# AUDIO_CODEC.net
KiCad netlist of a schematic drawn in Altium Designer
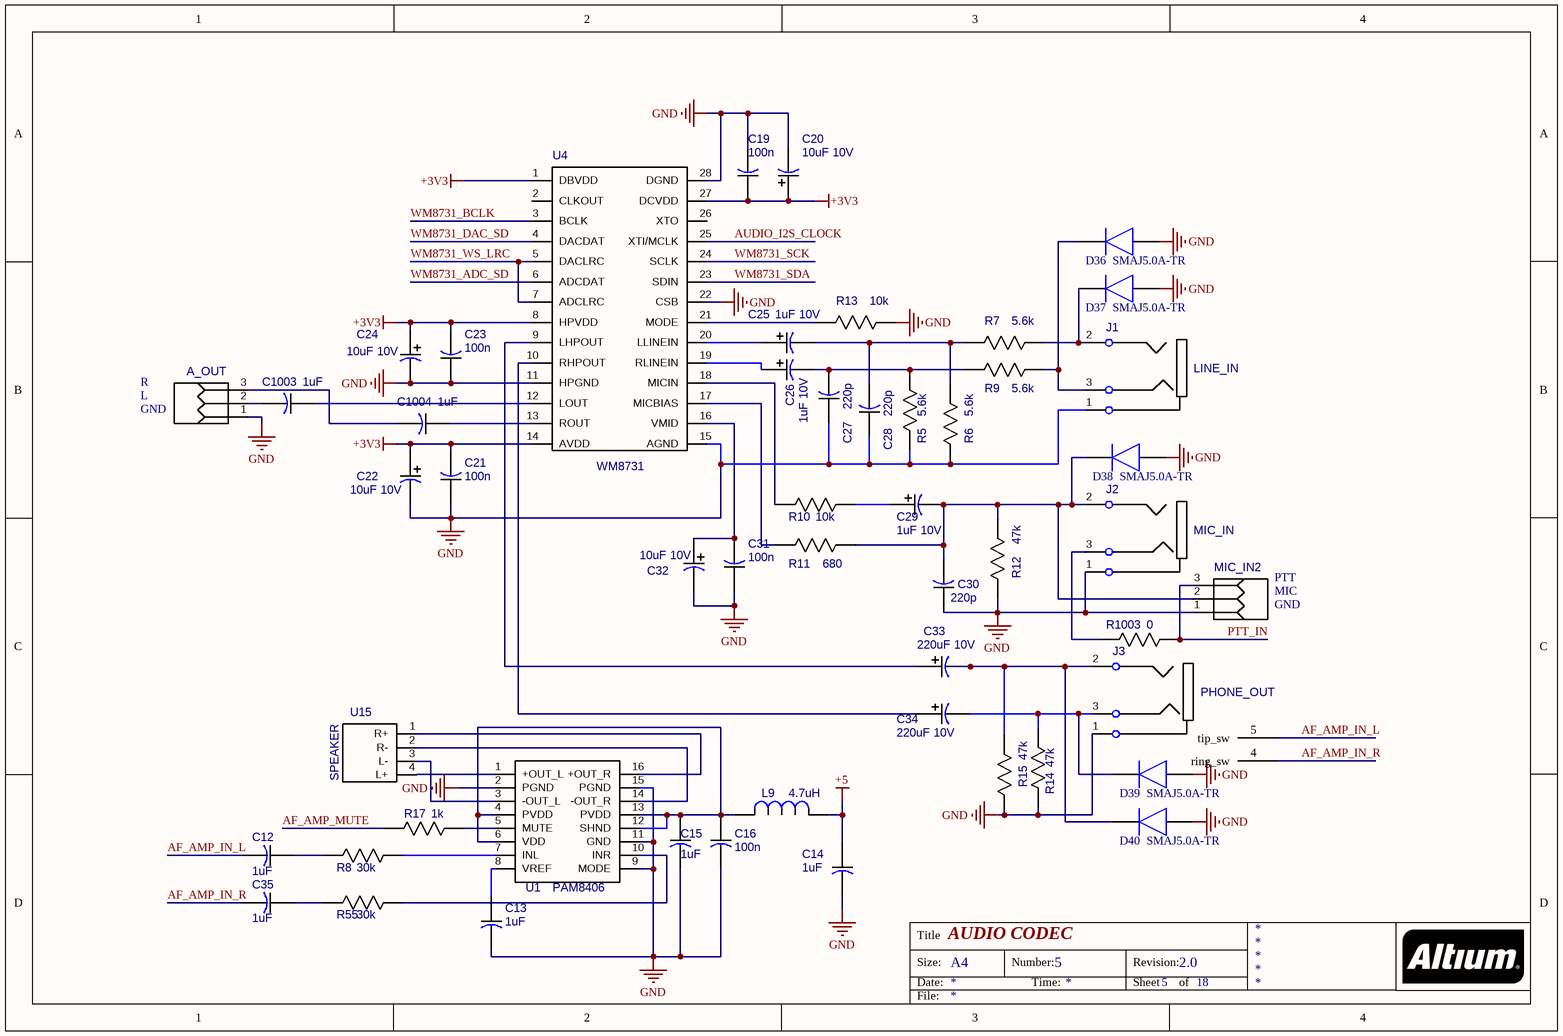
[diagram p0: AUDIO CODEC.SchDoc]

(export (version "E")
  (design (tool "Eeschema 10.0.6"))
  (components
    (comp (ref "A_OUT")
      (value "51022-0300_1")
      (footprint "51022-0200 - duplicate")
      (description "51022-0300")
      (libsource (lib "MOTHERBOARD") (part "51022-0300_1"))
    )
    (comp (ref "C12")
      (value "1uF")
      (footprint "CAP_0805")
      (description "CAP_0805")
      (libsource (lib "*") (part "CAP_0805"))
    )
    (comp (ref "C13")
      (value "1uF")
      (footprint "CAP_0805")
      (description "CAP_0805")
      (libsource (lib "*") (part "CAP_0805"))
    )
    (comp (ref "C14")
      (value "1uF")
      (footprint "CAP_0805")
      (description "CAP_0805")
      (libsource (lib "*") (part "CAP_0805"))
    )
    (comp (ref "C15")
      (value "1uF")
      (footprint "CAP_0805")
      (description "CAP_0805")
      (libsource (lib "*") (part "CAP_0805"))
    )
    (comp (ref "C16")
      (value "100n")
      (footprint "CAP_0805")
      (description "CAP_0805")
      (libsource (lib "*") (part "CAP_0805"))
    )
    (comp (ref "C19")
      (value "100n")
      (footprint "CAP_0805")
      (description "CAP_0805")
      (libsource (lib "*") (part "CAP_0805"))
    )
    (comp (ref "C20")
      (value "10uF 10V")
      (footprint "CAPAE_4.3x4.3h5.4")
      (description "CAPAE_4.3x4.3h5.4")
      (libsource (lib "*") (part "CAPAE_4.3x4.3h5.4"))
    )
    (comp (ref "C21")
      (value "100n")
      (footprint "CAP_0805")
      (description "CAP_0805")
      (libsource (lib "*") (part "CAP_0805"))
    )
    (comp (ref "C22")
      (value "10uF 10V")
      (footprint "CAPAE_4.3x4.3h5.4")
      (description "CAPAE_4.3x4.3h5.4")
      (libsource (lib "*") (part "CAPAE_4.3x4.3h5.4"))
    )
    (comp (ref "C23")
      (value "100n")
      (footprint "CAP_0805")
      (description "CAP_0805")
      (libsource (lib "*") (part "CAP_0805"))
    )
    (comp (ref "C24")
      (value "10uF 10V")
      (footprint "CAPAE_4.3x4.3h5.4")
      (description "CAPAE_4.3x4.3h5.4")
      (libsource (lib "*") (part "CAPAE_4.3x4.3h5.4"))
    )
    (comp (ref "C25")
      (value "1uF 10V")
      (footprint "CAPAE_4.3x4.3h5.4")
      (description "CAPAE_4.3x4.3h5.4")
      (libsource (lib "*") (part "CAPAE_4.3x4.3h5.4"))
    )
    (comp (ref "C26")
      (value "1uF 10V")
      (footprint "CAPAE_4.3x4.3h5.4")
      (description "CAPAE_4.3x4.3h5.4")
      (libsource (lib "*") (part "CAPAE_4.3x4.3h5.4"))
    )
    (comp (ref "C27")
      (value "220p")
      (footprint "CAP_0805")
      (description "CAP_0805")
      (libsource (lib "*") (part "CAP_0805"))
    )
    (comp (ref "C28")
      (value "220p")
      (footprint "CAP_0805")
      (description "CAP_0805")
      (libsource (lib "*") (part "CAP_0805"))
    )
    (comp (ref "C29")
      (value "1uF 10V")
      (footprint "CAPAE_4.3x4.3h5.4")
      (description "CAPAE_4.3x4.3h5.4")
      (libsource (lib "*") (part "CAPAE_4.3x4.3h5.4"))
    )
    (comp (ref "C30")
      (value "220p")
      (footprint "CAP_0805")
      (description "CAP_0805")
      (libsource (lib "*") (part "CAP_0805"))
    )
    (comp (ref "C31")
      (value "100n")
      (footprint "CAP_0805")
      (description "CAP_0805")
      (libsource (lib "*") (part "CAP_0805"))
    )
    (comp (ref "C32")
      (value "10uF 10V")
      (footprint "CAPAE_4.3x4.3h5.4")
      (description "CAPAE_4.3x4.3h5.4")
      (libsource (lib "*") (part "CAPAE_4.3x4.3h5.4"))
    )
    (comp (ref "C33")
      (value "220uF 10V")
      (footprint "EEEFC_sizeС")
      (description "CAPAE_4.3x4.3h5.4")
      (libsource (lib "*") (part "CAPAE_4.3x4.3h5.4"))
    )
    (comp (ref "C34")
      (value "220uF 10V")
      (footprint "EEEFC_sizeС")
      (description "CAPAE_4.3x4.3h5.4")
      (libsource (lib "*") (part "CAPAE_4.3x4.3h5.4"))
    )
    (comp (ref "C35")
      (value "1uF")
      (footprint "CAP_0805")
      (description "CAP_0805")
      (libsource (lib "*") (part "CAP_0805"))
    )
    (comp (ref "C1003")
      (value "1uF")
      (footprint "CAP_0805")
      (description "CAP_0805")
      (libsource (lib "*") (part "CAP_0805"))
    )
    (comp (ref "C1004")
      (value "1uF")
      (footprint "CAP_0805")
      (description "CAP_0805")
      (libsource (lib "*") (part "CAP_0805"))
    )
    (comp (ref "D36")
      (value "SMAJ5.0A-TR")
      (footprint "SamacSys:SMBJ36CATR")
      (description "Diode")
      (fields
        (field (name "MANUFACTURER_PART_NUMBER") "SMLVT3V3")
        (field (name "MOUSER PART NUMBER") "511-SMLVT3V3")
      )
      (libsource (lib "*") (part "SMLVT3V3"))
    )
    (comp (ref "D37")
      (value "SMAJ5.0A-TR")
      (footprint "SamacSys:SMBJ36CATR")
      (description "Diode")
      (fields
        (field (name "MANUFACTURER_PART_NUMBER") "SMLVT3V3")
        (field (name "MOUSER PART NUMBER") "511-SMLVT3V3")
      )
      (libsource (lib "*") (part "SMLVT3V3"))
    )
    (comp (ref "D38")
      (value "SMAJ5.0A-TR")
      (footprint "SamacSys:SMBJ36CATR")
      (description "Diode")
      (fields
        (field (name "MANUFACTURER_PART_NUMBER") "SMLVT3V3")
        (field (name "MOUSER PART NUMBER") "511-SMLVT3V3")
      )
      (libsource (lib "*") (part "SMLVT3V3"))
    )
    (comp (ref "D39")
      (value "SMAJ5.0A-TR")
      (footprint "SamacSys:SMBJ36CATR")
      (description "Diode")
      (fields
        (field (name "MANUFACTURER_PART_NUMBER") "SMLVT3V3")
        (field (name "MOUSER PART NUMBER") "511-SMLVT3V3")
      )
      (libsource (lib "*") (part "SMLVT3V3"))
    )
    (comp (ref "D40")
      (value "SMAJ5.0A-TR")
      (footprint "SamacSys:SMBJ36CATR")
      (description "Diode")
      (fields
        (field (name "MANUFACTURER_PART_NUMBER") "SMLVT3V3")
        (field (name "MOUSER PART NUMBER") "511-SMLVT3V3")
      )
      (libsource (lib "*") (part "SMLVT3V3"))
    )
    (comp (ref "J1")
      (value "LINE_IN")
      (footprint "SJ1-3525NG")
      (description "SJ1-3525NG")
      (libsource (lib "*") (part "SJ1-3523N"))
    )
    (comp (ref "J2")
      (value "MIC_IN")
      (footprint "SJ1-3525NG")
      (description "SJ1-3525NG")
      (libsource (lib "*") (part "SJ1-3523N"))
    )
    (comp (ref "J3")
      (value "PHONE_OUT")
      (footprint "SJ1-3525NG")
      (description "SJ1-3525NG")
      (libsource (lib "") (part "SJ1-3523N_1"))
    )
    (comp (ref "L9")
      (value "4.7uH")
      (footprint "IND_1812")
      (description "IND_1812")
      (fields (field (name "Comment") "3.3uH"))
      (libsource (lib "*") (part "IND_1812"))
    )
    (comp (ref "MIC_IN2")
      (value "51022-0300_1")
      (footprint "51022-0200 - duplicate")
      (description "51022-0300")
      (libsource (lib "MOTHERBOARD") (part "51022-0300_1"))
    )
    (comp (ref "R5")
      (value "5.6k")
      (footprint "RES_0805")
      (description "RES_0805")
      (libsource (lib "*") (part "RES_0805"))
    )
    (comp (ref "R6")
      (value "5.6k")
      (footprint "RES_0805")
      (description "RES_0805")
      (libsource (lib "*") (part "RES_0805"))
    )
    (comp (ref "R7")
      (value "5.6k")
      (footprint "RES_0805")
      (description "RES_0805")
      (libsource (lib "*") (part "RES_0805"))
    )
    (comp (ref "R8")
      (value "30k")
      (footprint "RES_0805")
      (description "RES_0805")
      (libsource (lib "*") (part "RES_0805"))
    )
    (comp (ref "R9")
      (value "5.6k")
      (footprint "RES_0805")
      (description "RES_0805")
      (libsource (lib "*") (part "RES_0805"))
    )
    (comp (ref "R10")
      (value "10k")
      (footprint "RES_0805")
      (description "RES_0805")
      (libsource (lib "*") (part "RES_0805"))
    )
    (comp (ref "R11")
      (value "680")
      (footprint "RES_0805")
      (description "RES_0805")
      (libsource (lib "*") (part "RES_0805"))
    )
    (comp (ref "R12")
      (value "47k")
      (footprint "RES_0805")
      (description "RES_0805")
      (libsource (lib "*") (part "RES_0805"))
    )
    (comp (ref "R13")
      (value "10k")
      (footprint "RES_0805")
      (description "RES_0805")
      (libsource (lib "*") (part "RES_0805"))
    )
    (comp (ref "R14")
      (value "47k")
      (footprint "RES_0805")
      (description "RES_0805")
      (libsource (lib "*") (part "RES_0805"))
    )
    (comp (ref "R15")
      (value "47k")
      (footprint "RES_0805")
      (description "RES_0805")
      (libsource (lib "*") (part "RES_0805"))
    )
    (comp (ref "R17")
      (value "1k")
      (footprint "RES_0805")
      (description "RES_0805")
      (libsource (lib "*") (part "RES_0805"))
    )
    (comp (ref "R55")
      (value "30k")
      (footprint "RES_0805")
      (description "RES_0805")
      (libsource (lib "*") (part "RES_0805"))
    )
    (comp (ref "R1003")
      (value "0")
      (footprint "RES_0805")
      (description "RES_0805")
      (libsource (lib "*") (part "RES_0805"))
    )
    (comp (ref "U1") (value "PAM8406") (footprint "PAM8403") (libsource (lib "MOTHERBOARD") (part "PAM8406")))
    (comp (ref "U4") (value "WM8731") (footprint "WM8731") (libsource (lib "*") (part "WM8731")))
    (comp (ref "U15")
      (value "SPEAKER")
      (footprint "speaker conn")
      (description "4 pins conn")
      (libsource (lib "MOTHERBOARD") (part "speaker conn"))
    )
  )
  (nets
    (net (code "1") (name "+3V3") (class "Default")
      (node (ref "C19") (pin "1") (pinfunction "1_1") (pintype "passive"))
      (node (ref "C20") (pin "1") (pinfunction "PLUS_1") (pintype "passive"))
      (node (ref "C21") (pin "2") (pinfunction "2_2") (pintype "passive"))
      (node (ref "C22") (pin "1") (pinfunction "PLUS_1") (pintype "passive"))
      (node (ref "C23") (pin "2") (pinfunction "2_2") (pintype "passive"))
      (node (ref "C24") (pin "1") (pinfunction "PLUS_1") (pintype "passive"))
      (node (ref "U4") (pin "1") (pinfunction "DBVDD_1") (pintype "passive"))
      (node (ref "U4") (pin "14") (pinfunction "AVDD_14") (pintype "passive"))
      (node (ref "U4") (pin "27") (pinfunction "DCVDD_27") (pintype "passive"))
      (node (ref "U4") (pin "8") (pinfunction "HPVDD_8") (pintype "passive"))
    )
    (net (code "2") (name "+5") (class "Default")
      (node (ref "C14") (pin "1") (pinfunction "1_1") (pintype "passive"))
      (node (ref "L9") (pin "2") (pinfunction "2_2") (pintype "passive"))
    )
    (net (code "3") (name "/AF_AMP_IN_L") (class "Default")
      (node (ref "C12") (pin "2") (pinfunction "2_2") (pintype "passive"))
      (node (ref "J3") (pin "5") (pinfunction "tip_sw_5") (pintype "passive"))
    )
    (net (code "4") (name "/AF_AMP_IN_R") (class "Default")
      (node (ref "C35") (pin "2") (pinfunction "2_2") (pintype "passive"))
      (node (ref "J3") (pin "4") (pinfunction "ring_sw_4") (pintype "passive"))
    )
    (net (code "5") (name "/AF_AMP_MUTE") (class "Default")
      (node (ref "R17") (pin "2") (pinfunction "2_2") (pintype "passive"))
    )
    (net (code "6") (name "/AUDIO_I2S_CLOCK") (class "Default")
      (node (ref "U4") (pin "25") (pinfunction "XTI/MCLK_25") (pintype "passive"))
    )
    (net (code "7") (name "/PTT_IN") (class "Default")
      (node (ref "MIC_IN2") (pin "3") (pintype "passive"))
      (node (ref "R1003") (pin "2") (pinfunction "2_2") (pintype "passive"))
    )
    (net (code "8") (name "/WM8731_ADC_SD") (class "Default")
      (node (ref "U4") (pin "6") (pinfunction "ADCDAT_6") (pintype "passive"))
    )
    (net (code "9") (name "/WM8731_BCLK") (class "Default")
      (node (ref "U4") (pin "3") (pinfunction "BCLK_3") (pintype "passive"))
    )
    (net (code "10") (name "/WM8731_DAC_SD") (class "Default")
      (node (ref "U4") (pin "4") (pinfunction "DACDAT_4") (pintype "passive"))
    )
    (net (code "11") (name "/WM8731_SCK") (class "Default")
      (node (ref "U4") (pin "24") (pinfunction "SCLK_24") (pintype "passive"))
    )
    (net (code "12") (name "/WM8731_SDA") (class "Default")
      (node (ref "U4") (pin "23") (pinfunction "SDIN_23") (pintype "passive"))
    )
    (net (code "13") (name "/WM8731_WS_LRC") (class "Default")
      (node (ref "U4") (pin "5") (pinfunction "DACLRC_5") (pintype "passive"))
      (node (ref "U4") (pin "7") (pinfunction "ADCLRC_7") (pintype "passive"))
    )
    (net (code "14") (name "GND") (class "Default")
      (node (ref "A_OUT") (pin "1") (pintype "passive"))
      (node (ref "C13") (pin "2") (pinfunction "2_2") (pintype "passive"))
      (node (ref "C14") (pin "2") (pinfunction "2_2") (pintype "passive"))
      (node (ref "C15") (pin "2") (pinfunction "2_2") (pintype "passive"))
      (node (ref "C16") (pin "2") (pinfunction "2_2") (pintype "passive"))
      (node (ref "C19") (pin "2") (pinfunction "2_2") (pintype "passive"))
      (node (ref "C20") (pin "2") (pinfunction "MINUS_2") (pintype "passive"))
      (node (ref "C21") (pin "1") (pinfunction "1_1") (pintype "passive"))
      (node (ref "C22") (pin "2") (pinfunction "MINUS_2") (pintype "passive"))
      (node (ref "C23") (pin "1") (pinfunction "1_1") (pintype "passive"))
      (node (ref "C24") (pin "2") (pinfunction "MINUS_2") (pintype "passive"))
      (node (ref "C27") (pin "1") (pinfunction "1_1") (pintype "passive"))
      (node (ref "C28") (pin "1") (pinfunction "1_1") (pintype "passive"))
      (node (ref "C30") (pin "1") (pinfunction "1_1") (pintype "passive"))
      (node (ref "C31") (pin "1") (pinfunction "1_1") (pintype "passive"))
      (node (ref "C32") (pin "2") (pinfunction "MINUS_2") (pintype "passive"))
      (node (ref "D36") (pin "2") (pinfunction "A_2") (pintype "passive"))
      (node (ref "D37") (pin "2") (pinfunction "A_2") (pintype "passive"))
      (node (ref "D38") (pin "2") (pinfunction "A_2") (pintype "passive"))
      (node (ref "D39") (pin "2") (pinfunction "A_2") (pintype "passive"))
      (node (ref "D40") (pin "2") (pinfunction "A_2") (pintype "passive"))
      (node (ref "J1") (pin "1") (pinfunction "sleeve_1") (pintype "passive"))
      (node (ref "J2") (pin "1") (pinfunction "sleeve_1") (pintype "passive"))
      (node (ref "J3") (pin "1") (pinfunction "sleeve_1") (pintype "passive"))
      (node (ref "MIC_IN2") (pin "1") (pintype "passive"))
      (node (ref "R12") (pin "1") (pinfunction "1_1") (pintype "passive"))
      (node (ref "R13") (pin "1") (pinfunction "1_1") (pintype "passive"))
      (node (ref "R14") (pin "1") (pinfunction "1_1") (pintype "passive"))
      (node (ref "R15") (pin "1") (pinfunction "1_1") (pintype "passive"))
      (node (ref "R5") (pin "1") (pinfunction "1_1") (pintype "passive"))
      (node (ref "R6") (pin "1") (pinfunction "1_1") (pintype "passive"))
      (node (ref "U1") (pin "11") (pinfunction "GND_11") (pintype "passive"))
      (node (ref "U1") (pin "15") (pinfunction "PGND_15") (pintype "passive"))
      (node (ref "U1") (pin "2") (pinfunction "PGND_2") (pintype "passive"))
      (node (ref "U1") (pin "9") (pinfunction "MODE_9") (pintype "passive"))
      (node (ref "U4") (pin "11") (pinfunction "HPGND_11") (pintype "passive"))
      (node (ref "U4") (pin "15") (pinfunction "AGND_15") (pintype "passive"))
      (node (ref "U4") (pin "22") (pinfunction "CSB_22") (pintype "passive"))
      (node (ref "U4") (pin "28") (pinfunction "DGND_28") (pintype "passive"))
    )
    (net (code "15") (name "Net-(A_OUT-Pad2)") (class "Default")
      (node (ref "A_OUT") (pin "2") (pintype "passive"))
      (node (ref "C1003") (pin "2") (pinfunction "2_2") (pintype "passive"))
    )
    (net (code "16") (name "Net-(A_OUT-Pad3)") (class "Default")
      (node (ref "A_OUT") (pin "3") (pintype "passive"))
      (node (ref "C1004") (pin "2") (pinfunction "2_2") (pintype "passive"))
    )
    (net (code "17") (name "Net-(C12-Pad1)") (class "Default")
      (node (ref "C12") (pin "1") (pinfunction "1_1") (pintype "passive"))
      (node (ref "R8") (pin "2") (pinfunction "2_2") (pintype "passive"))
    )
    (net (code "18") (name "Net-(C25-MINUS)") (class "Default")
      (node (ref "C25") (pin "2") (pinfunction "MINUS_2") (pintype "passive"))
      (node (ref "C28") (pin "2") (pinfunction "2_2") (pintype "passive"))
      (node (ref "R6") (pin "2") (pinfunction "2_2") (pintype "passive"))
      (node (ref "R7") (pin "2") (pinfunction "2_2") (pintype "passive"))
    )
    (net (code "19") (name "Net-(C25-PLUS)") (class "Default")
      (node (ref "C25") (pin "1") (pinfunction "PLUS_1") (pintype "passive"))
      (node (ref "U4") (pin "20") (pinfunction "LLINEIN_20") (pintype "passive"))
    )
    (net (code "20") (name "Net-(C26-MINUS)") (class "Default")
      (node (ref "C26") (pin "2") (pinfunction "MINUS_2") (pintype "passive"))
      (node (ref "C27") (pin "2") (pinfunction "2_2") (pintype "passive"))
      (node (ref "R5") (pin "2") (pinfunction "2_2") (pintype "passive"))
      (node (ref "R9") (pin "2") (pinfunction "2_2") (pintype "passive"))
    )
    (net (code "21") (name "Net-(C26-PLUS)") (class "Default")
      (node (ref "C26") (pin "1") (pinfunction "PLUS_1") (pintype "passive"))
      (node (ref "U4") (pin "19") (pinfunction "RLINEIN_19") (pintype "passive"))
    )
    (net (code "22") (name "Net-(C29-MINUS)") (class "Default")
      (node (ref "C29") (pin "2") (pinfunction "MINUS_2") (pintype "passive"))
      (node (ref "C30") (pin "2") (pinfunction "2_2") (pintype "passive"))
      (node (ref "D38") (pin "1") (pinfunction "K_1") (pintype "passive"))
      (node (ref "J2") (pin "2") (pinfunction "tip_2") (pintype "passive"))
      (node (ref "MIC_IN2") (pin "2") (pintype "passive"))
      (node (ref "R11") (pin "1") (pinfunction "1_1") (pintype "passive"))
      (node (ref "R12") (pin "2") (pinfunction "2_2") (pintype "passive"))
    )
    (net (code "23") (name "Net-(C29-PLUS)") (class "Default")
      (node (ref "C29") (pin "1") (pinfunction "PLUS_1") (pintype "passive"))
      (node (ref "R10") (pin "1") (pinfunction "1_1") (pintype "passive"))
    )
    (net (code "24") (name "Net-(C32-PLUS)") (class "Default")
      (node (ref "C31") (pin "2") (pinfunction "2_2") (pintype "passive"))
      (node (ref "C32") (pin "1") (pinfunction "PLUS_1") (pintype "passive"))
      (node (ref "U4") (pin "16") (pinfunction "VMID_16") (pintype "passive"))
    )
    (net (code "25") (name "Net-(C33-MINUS)") (class "Default")
      (node (ref "C33") (pin "2") (pinfunction "MINUS_2") (pintype "passive"))
      (node (ref "D40") (pin "1") (pinfunction "K_1") (pintype "passive"))
      (node (ref "J3") (pin "2") (pinfunction "tip_2") (pintype "passive"))
      (node (ref "R15") (pin "2") (pinfunction "2_2") (pintype "passive"))
    )
    (net (code "26") (name "Net-(C33-PLUS)") (class "Default")
      (node (ref "C33") (pin "1") (pinfunction "PLUS_1") (pintype "passive"))
      (node (ref "U4") (pin "9") (pinfunction "LHPOUT_9") (pintype "passive"))
    )
    (net (code "27") (name "Net-(C34-MINUS)") (class "Default")
      (node (ref "C34") (pin "2") (pinfunction "MINUS_2") (pintype "passive"))
      (node (ref "D39") (pin "1") (pinfunction "K_1") (pintype "passive"))
      (node (ref "J3") (pin "3") (pinfunction "ring_3") (pintype "passive"))
      (node (ref "R14") (pin "2") (pinfunction "2_2") (pintype "passive"))
    )
    (net (code "28") (name "Net-(C34-PLUS)") (class "Default")
      (node (ref "C34") (pin "1") (pinfunction "PLUS_1") (pintype "passive"))
      (node (ref "U4") (pin "10") (pinfunction "RHPOUT_10") (pintype "passive"))
    )
    (net (code "29") (name "Net-(C35-Pad1)") (class "Default")
      (node (ref "C35") (pin "1") (pinfunction "1_1") (pintype "passive"))
      (node (ref "R55") (pin "2") (pinfunction "2_2") (pintype "passive"))
    )
    (net (code "30") (name "Net-(D36-K)") (class "Default")
      (node (ref "D36") (pin "1") (pinfunction "K_1") (pintype "passive"))
      (node (ref "J1") (pin "3") (pinfunction "ring_3") (pintype "passive"))
      (node (ref "R9") (pin "1") (pinfunction "1_1") (pintype "passive"))
    )
    (net (code "31") (name "Net-(D37-K)") (class "Default")
      (node (ref "D37") (pin "1") (pinfunction "K_1") (pintype "passive"))
      (node (ref "J1") (pin "2") (pinfunction "tip_2") (pintype "passive"))
      (node (ref "R7") (pin "1") (pinfunction "1_1") (pintype "passive"))
    )
    (net (code "32") (name "Net-(J2-ring)") (class "Default")
      (node (ref "J2") (pin "3") (pinfunction "ring_3") (pintype "passive"))
      (node (ref "R1003") (pin "1") (pinfunction "1_1") (pintype "passive"))
    )
    (net (code "33") (name "Net-(U1-+OUT_L)") (class "Default")
      (node (ref "U1") (pin "1") (pinfunction "+OUT_L_1") (pintype "passive"))
      (node (ref "U15") (pin "4") (pinfunction "L+_4") (pintype "passive"))
    )
    (net (code "34") (name "Net-(U1-+OUT_R)") (class "Default")
      (node (ref "U1") (pin "16") (pinfunction "+OUT_R_16") (pintype "passive"))
      (node (ref "U15") (pin "1") (pinfunction "R+_1") (pintype "passive"))
    )
    (net (code "35") (name "Net-(U1--OUT_L)") (class "Default")
      (node (ref "U1") (pin "3") (pinfunction "-OUT_L_3") (pintype "passive"))
      (node (ref "U15") (pin "3") (pinfunction "L-_3") (pintype "passive"))
    )
    (net (code "36") (name "Net-(U1--OUT_R)") (class "Default")
      (node (ref "U1") (pin "14") (pinfunction "-OUT_R_14") (pintype "passive"))
      (node (ref "U15") (pin "2") (pinfunction "R-_2") (pintype "passive"))
    )
    (net (code "37") (name "Net-(U1-INL)") (class "Default")
      (node (ref "R8") (pin "1") (pinfunction "1_1") (pintype "passive"))
      (node (ref "U1") (pin "7") (pinfunction "INL_7") (pintype "passive"))
    )
    (net (code "38") (name "Net-(U1-INR)") (class "Default")
      (node (ref "R55") (pin "1") (pinfunction "1_1") (pintype "passive"))
      (node (ref "U1") (pin "10") (pinfunction "INR_10") (pintype "passive"))
    )
    (net (code "39") (name "Net-(U1-MUTE)") (class "Default")
      (node (ref "R17") (pin "1") (pinfunction "1_1") (pintype "passive"))
      (node (ref "U1") (pin "5") (pinfunction "MUTE_5") (pintype "passive"))
    )
    (net (code "40") (name "Net-(U1-SHND)") (class "Default")
      (node (ref "C15") (pin "1") (pinfunction "1_1") (pintype "passive"))
      (node (ref "C16") (pin "1") (pinfunction "1_1") (pintype "passive"))
      (node (ref "L9") (pin "1") (pinfunction "1_1") (pintype "passive"))
      (node (ref "U1") (pin "12") (pinfunction "SHND_12") (pintype "passive"))
      (node (ref "U1") (pin "13") (pinfunction "PVDD_13") (pintype "passive"))
      (node (ref "U1") (pin "4") (pinfunction "PVDD_4") (pintype "passive"))
      (node (ref "U1") (pin "6") (pinfunction "VDD_6") (pintype "passive"))
    )
    (net (code "41") (name "Net-(U1-VREF)") (class "Default")
      (node (ref "C13") (pin "1") (pinfunction "1_1") (pintype "passive"))
      (node (ref "U1") (pin "8") (pinfunction "VREF_8") (pintype "passive"))
    )
    (net (code "42") (name "Net-(U4-LOUT)") (class "Default")
      (node (ref "C1003") (pin "1") (pinfunction "1_1") (pintype "passive"))
      (node (ref "U4") (pin "12") (pinfunction "LOUT_12") (pintype "passive"))
    )
    (net (code "43") (name "Net-(U4-MICBIAS)") (class "Default")
      (node (ref "R11") (pin "2") (pinfunction "2_2") (pintype "passive"))
      (node (ref "U4") (pin "17") (pinfunction "MICBIAS_17") (pintype "passive"))
    )
    (net (code "44") (name "Net-(U4-MICIN)") (class "Default")
      (node (ref "R10") (pin "2") (pinfunction "2_2") (pintype "passive"))
      (node (ref "U4") (pin "18") (pinfunction "MICIN_18") (pintype "passive"))
    )
    (net (code "45") (name "Net-(U4-MODE)") (class "Default")
      (node (ref "R13") (pin "2") (pinfunction "2_2") (pintype "passive"))
      (node (ref "U4") (pin "21") (pinfunction "MODE_21") (pintype "passive"))
    )
    (net (code "46") (name "Net-(U4-ROUT)") (class "Default")
      (node (ref "C1004") (pin "1") (pinfunction "1_1") (pintype "passive"))
      (node (ref "U4") (pin "13") (pinfunction "ROUT_13") (pintype "passive"))
    )
    (net (code "47") (name "unconnected-(U4-CLKOUT-Pad2)") (class "Default")
      (node (ref "U4") (pin "2") (pinfunction "CLKOUT_2") (pintype "passive"))
    )
    (net (code "48") (name "unconnected-(U4-XTO-Pad26)") (class "Default")
      (node (ref "U4") (pin "26") (pinfunction "XTO_26") (pintype "passive"))
    )
  )
)
